# SymphonyLights_SOC.net
KiCad netlist of a schematic drawn in Altium Designer
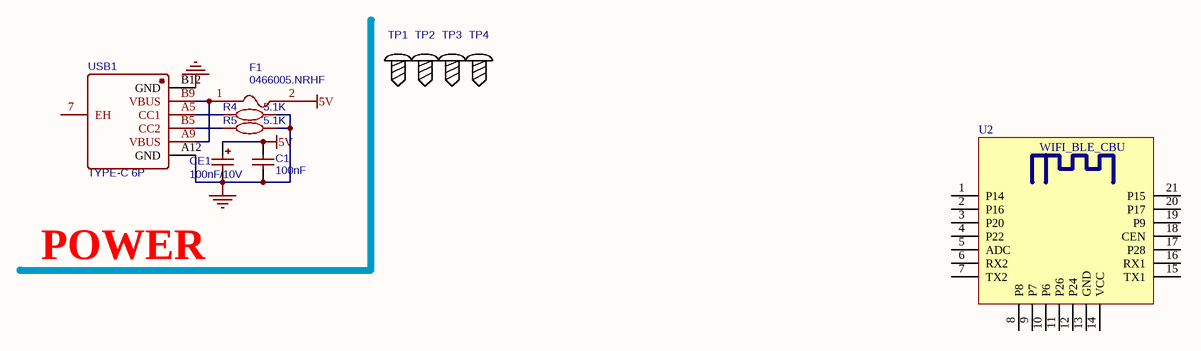
[diagram p0: SymphonyLights_SOC.SchDoc]

(export (version "E")
  (design (tool "Eeschema 10.0.6"))
  (components
    (comp (ref "C1")
      (value "100nF")
      (footprint "0805C")
      (fields
        (field (name "BOM_MANUFACTURER PART") "0805B104K500NT")
        (field (name "BOM_SUPPLIER PART") "C38141")
      )
      (libsource (lib "altium-import") (part "root_1_100nF_"))
    )
    (comp (ref "CE1")
      (value "100nF/10V")
      (footprint "EC2.5/6")
      (fields
        (field (name "BOM_MANUFACTURER PART") "CA45-A-10V-22uF-K")
        (field (name "BOM_SUPPLIER PART") "C129272")
        (field (name "CONTRIBUTOR") "LCSC")
      )
      (libsource (lib "altium-import") (part "root_1_0.1uF_"))
    )
    (comp (ref "F1")
      (value "0466005.NRHF")
      (footprint "1206F")
      (fields (field (name "BOM_SUPPLIER PART") "C57525"))
      (libsource (lib "altium-import") (part "root_0_0466005.NRHF_"))
    )
    (comp (ref "R4")
      (value "5.1K")
      (footprint "0805R")
      (fields
        (field (name "BOM_SUPPLIER PART") "C328298")
        (field (name "BOM_MANUFACTURER PART") "AECR0402F10K0K9")
        (field (name "CONTRIBUTOR") "LCSC")
      )
      (libsource (lib "altium-import") (part "root_0_10K_"))
    )
    (comp (ref "R5")
      (value "5.1K")
      (footprint "0805R")
      (fields
        (field (name "BOM_SUPPLIER PART") "C328298")
        (field (name "BOM_MANUFACTURER PART") "AECR0402F10K0K9")
        (field (name "CONTRIBUTOR") "LCSC")
      )
      (libsource (lib "altium-import") (part "root_0_10K_"))
    )
    (comp (ref "TP1")
      (value "~")
      (footprint "M3螺丝孔")
      (fields (field (name "CONTRIBUTOR") "455553Z"))
      (libsource (lib "altium-import") (part "root_0__"))
    )
    (comp (ref "TP2")
      (value "~")
      (footprint "M3螺丝孔")
      (fields (field (name "CONTRIBUTOR") "455553Z"))
      (libsource (lib "altium-import") (part "root_0__"))
    )
    (comp (ref "TP3")
      (value "~")
      (footprint "M3螺丝孔")
      (fields (field (name "CONTRIBUTOR") "455553Z"))
      (libsource (lib "altium-import") (part "root_0__"))
    )
    (comp (ref "TP4")
      (value "~")
      (footprint "M3螺丝孔")
      (fields (field (name "CONTRIBUTOR") "455553Z"))
      (libsource (lib "altium-import") (part "root_0__"))
    )
    (comp (ref "U2")
      (value "WIFI_BLE_CBU")
      (footprint "WIFI_BLE_CBU")
      (description "Module")
      (libsource (lib "TYModeSchlib V03") (part "WIFI_BLE_CBU"))
    )
    (comp (ref "USB1")
      (value "TYPE-C 6P")
      (footprint "TYPE-C-SMD_TYPE-C-6P")
      (fields
        (field (name "BOM_SUPPLIER PART") "C668623")
        (field (name "BOM_MANUFACTURER PART") "TYPE-C 6P(073)")
        (field (name "CONTRIBUTOR") "LCSC")
      )
      (libsource (lib "altium-import") (part "root_0_mirrored_TYPE-C 6P(073)_"))
    )
  )
  (nets
    (net (code "1") (name "5V") (class "Default")
      (node (ref "C1") (pin "2") (pinfunction "2_2") (pintype "passive"))
      (node (ref "CE1") (pin "1") (pinfunction "1_1") (pintype "passive"))
      (node (ref "F1") (pin "2") (pinfunction "2_2") (pintype "passive"))
    )
    (net (code "2") (name "GND") (class "Default")
      (node (ref "C1") (pin "1") (pinfunction "1_1") (pintype "passive"))
      (node (ref "CE1") (pin "2") (pinfunction "2_2") (pintype "passive"))
      (node (ref "R4") (pin "2") (pinfunction "2_2") (pintype "passive"))
      (node (ref "R5") (pin "2") (pinfunction "2_2") (pintype "passive"))
      (node (ref "USB1") (pin "A12") (pinfunction "GND_A12") (pintype "passive"))
      (node (ref "USB1") (pin "B12") (pinfunction "GND_B12") (pintype "passive"))
    )
    (net (code "3") (name "Net-(F1-Pad1)") (class "Default")
      (node (ref "F1") (pin "1") (pinfunction "1_1") (pintype "passive"))
      (node (ref "USB1") (pin "A9") (pinfunction "VBUS_A9") (pintype "passive"))
      (node (ref "USB1") (pin "B9") (pinfunction "VBUS_B9") (pintype "passive"))
    )
    (net (code "4") (name "Net-(USB1-CC1)") (class "Default")
      (node (ref "R4") (pin "1") (pinfunction "1_1") (pintype "passive"))
      (node (ref "USB1") (pin "A5") (pinfunction "CC1_A5") (pintype "passive"))
    )
    (net (code "5") (name "Net-(USB1-CC2)") (class "Default")
      (node (ref "R5") (pin "1") (pinfunction "1_1") (pintype "passive"))
      (node (ref "USB1") (pin "B5") (pinfunction "CC2_B5") (pintype "passive"))
    )
    (net (code "6") (name "unconnected-(U2-ADC-Pad5)") (class "Default")
      (node (ref "U2") (pin "5") (pinfunction "ADC_5") (pintype "passive"))
    )
    (net (code "7") (name "unconnected-(U2-CEN-Pad18)") (class "Default")
      (node (ref "U2") (pin "18") (pinfunction "CEN_18") (pintype "passive"))
    )
    (net (code "8") (name "unconnected-(U2-GND-Pad13)") (class "Default")
      (node (ref "U2") (pin "13") (pinfunction "GND_13") (pintype "passive"))
    )
    (net (code "9") (name "unconnected-(U2-P6-Pad10)") (class "Default")
      (node (ref "U2") (pin "10") (pinfunction "P6_10") (pintype "passive"))
    )
    (net (code "10") (name "unconnected-(U2-P7-Pad9)") (class "Default")
      (node (ref "U2") (pin "9") (pinfunction "P7_9") (pintype "passive"))
    )
    (net (code "11") (name "unconnected-(U2-P8-Pad8)") (class "Default")
      (node (ref "U2") (pin "8") (pinfunction "P8_8") (pintype "passive"))
    )
    (net (code "12") (name "unconnected-(U2-P9-Pad19)") (class "Default")
      (node (ref "U2") (pin "19") (pinfunction "P9_19") (pintype "passive"))
    )
    (net (code "13") (name "unconnected-(U2-P14-Pad1)") (class "Default")
      (node (ref "U2") (pin "1") (pinfunction "P14_1") (pintype "passive"))
    )
    (net (code "14") (name "unconnected-(U2-P15-Pad21)") (class "Default")
      (node (ref "U2") (pin "21") (pinfunction "P15_21") (pintype "passive"))
    )
    (net (code "15") (name "unconnected-(U2-P16-Pad2)") (class "Default")
      (node (ref "U2") (pin "2") (pinfunction "P16_2") (pintype "passive"))
    )
    (net (code "16") (name "unconnected-(U2-P17-Pad20)") (class "Default")
      (node (ref "U2") (pin "20") (pinfunction "P17_20") (pintype "passive"))
    )
    (net (code "17") (name "unconnected-(U2-P20-Pad3)") (class "Default")
      (node (ref "U2") (pin "3") (pinfunction "P20_3") (pintype "passive"))
    )
    (net (code "18") (name "unconnected-(U2-P22-Pad4)") (class "Default")
      (node (ref "U2") (pin "4") (pinfunction "P22_4") (pintype "passive"))
    )
    (net (code "19") (name "unconnected-(U2-P24-Pad12)") (class "Default")
      (node (ref "U2") (pin "12") (pinfunction "P24_12") (pintype "passive"))
    )
    (net (code "20") (name "unconnected-(U2-P26-Pad11)") (class "Default")
      (node (ref "U2") (pin "11") (pinfunction "P26_11") (pintype "passive"))
    )
    (net (code "21") (name "unconnected-(U2-P28-Pad17)") (class "Default")
      (node (ref "U2") (pin "17") (pinfunction "P28_17") (pintype "passive"))
    )
    (net (code "22") (name "unconnected-(U2-RX1-Pad16)") (class "Default")
      (node (ref "U2") (pin "16") (pinfunction "RX1_16") (pintype "passive"))
    )
    (net (code "23") (name "unconnected-(U2-RX2-Pad6)") (class "Default")
      (node (ref "U2") (pin "6") (pinfunction "RX2_6") (pintype "passive"))
    )
    (net (code "24") (name "unconnected-(U2-TX1-Pad15)") (class "Default")
      (node (ref "U2") (pin "15") (pinfunction "TX1_15") (pintype "passive"))
    )
    (net (code "25") (name "unconnected-(U2-TX2-Pad7)") (class "Default")
      (node (ref "U2") (pin "7") (pinfunction "TX2_7") (pintype "passive"))
    )
    (net (code "26") (name "unconnected-(U2-VCC-Pad14)") (class "Default")
      (node (ref "U2") (pin "14") (pinfunction "VCC_14") (pintype "passive"))
    )
    (net (code "27") (name "unconnected-(USB1-EH-Pad7)") (class "Default")
      (node (ref "USB1") (pin "7") (pinfunction "EH_7") (pintype "passive"))
    )
  )
)
